# Wind_Weather_Station_V2_1.net
KiCad netlist of a schematic drawn in EAGLE
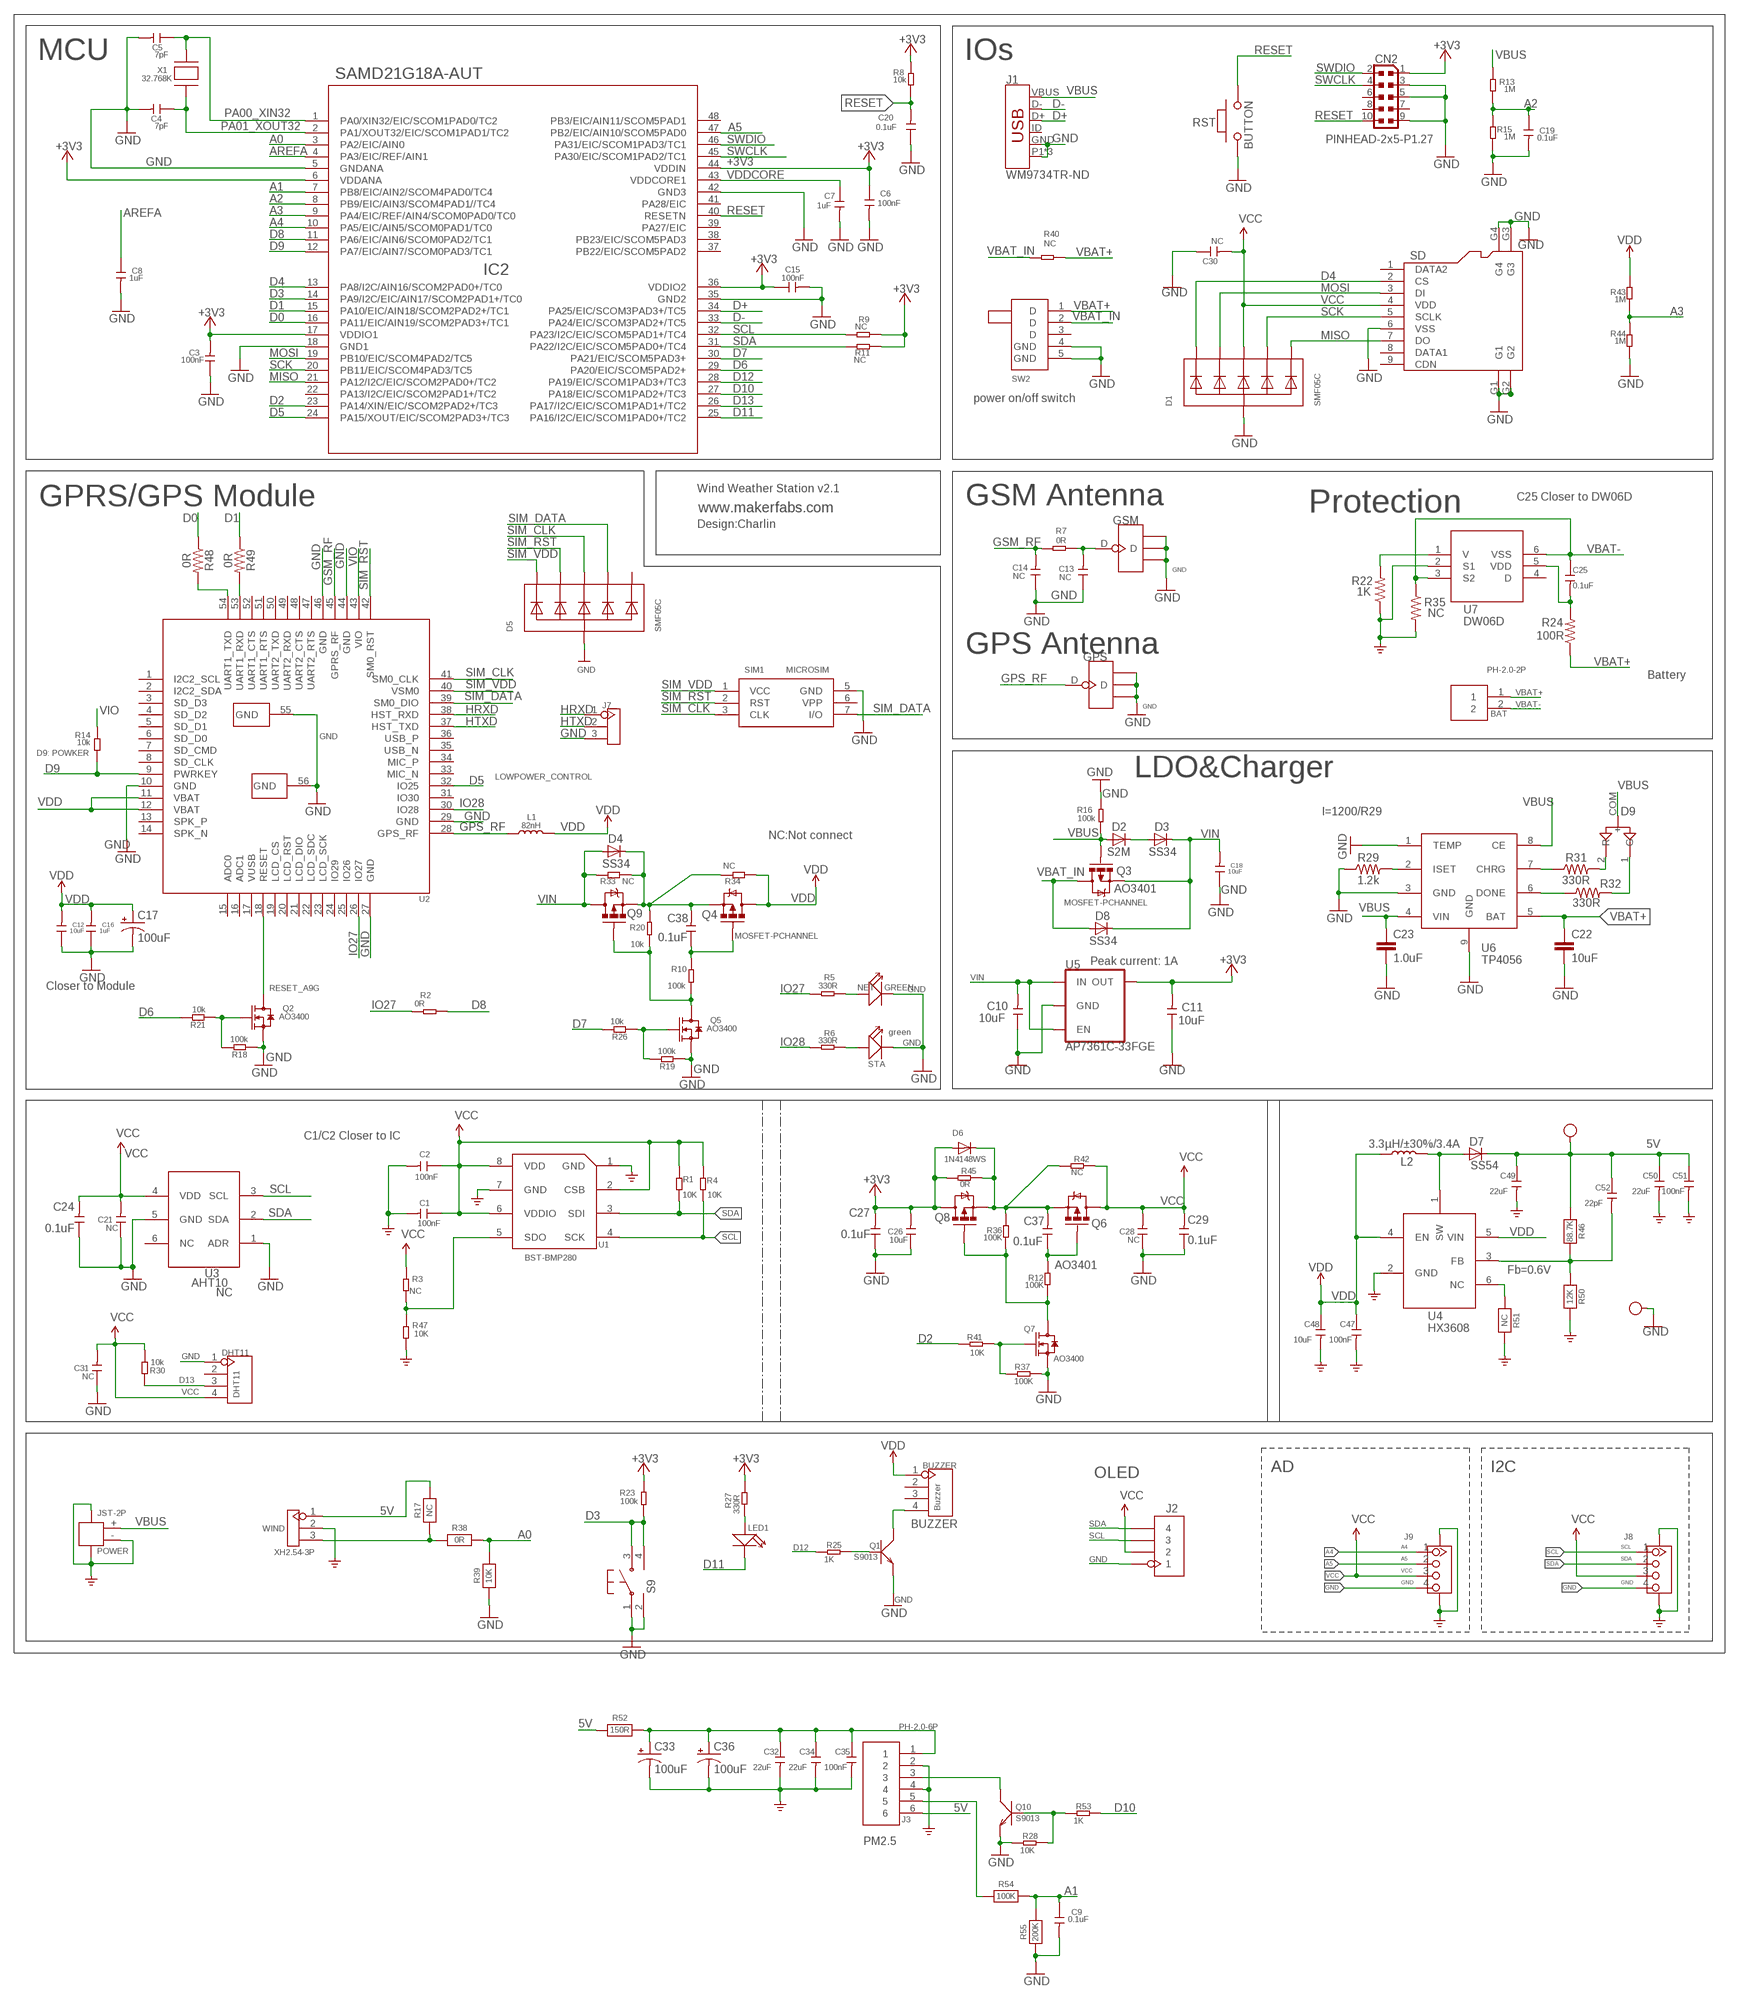
[diagram p0: schematic, sheet 1]

(export (version "E")
  (design (tool "Eeschema 10.0.6"))
  (components
    (comp (ref "5V")
      (value "TEST-POINT'4545'")
      (footprint "eagle-import:TP-D45MIL")
      (fields (field (name "PARTNO") "DNP"))
      (libsource (lib "eagle-import") (part "TEST-POINT'4545'"))
    )
    (comp (ref "BAT")
      (value "PH-2.0-2P")
      (footprint "eagle-import:PH-2.0-2P")
      (libsource (lib "eagle-import") (part "PH-2.0-2P"))
    )
    (comp (ref "BUZZER")
      (value "Buzzer")
      (footprint "eagle-import:4P-65_35ROUND")
      (libsource (lib "eagle-import") (part "HEADER-4P-60/35MILROUND"))
    )
    (comp (ref "C1")
      (value "100nF")
      (footprint "eagle-import:C0603")
      (libsource (lib "eagle-import") (part "CAP-0603"))
    )
    (comp (ref "C2")
      (value "100nF")
      (footprint "eagle-import:C0603")
      (libsource (lib "eagle-import") (part "CAP-0603"))
    )
    (comp (ref "C3")
      (value "100nF")
      (footprint "eagle-import:0603")
      (libsource (lib "eagle-import") (part "C-0603"))
    )
    (comp (ref "C4")
      (value "7pF")
      (footprint "eagle-import:0603")
      (libsource (lib "eagle-import") (part "C-0603"))
    )
    (comp (ref "C5")
      (value "7pF")
      (footprint "eagle-import:0603")
      (libsource (lib "eagle-import") (part "C-0603"))
    )
    (comp (ref "C6")
      (value "100nF")
      (footprint "eagle-import:0603")
      (libsource (lib "eagle-import") (part "C-0603"))
    )
    (comp (ref "C7")
      (value "1uF")
      (footprint "eagle-import:0603")
      (libsource (lib "eagle-import") (part "C-0603"))
    )
    (comp (ref "C8")
      (value "1uF")
      (footprint "eagle-import:0603")
      (libsource (lib "eagle-import") (part "C-0603"))
    )
    (comp (ref "C9")
      (value "0.1uF")
      (footprint "eagle-import:0603")
      (libsource (lib "eagle-import") (part "C-0603"))
    )
    (comp (ref "C10")
      (value "10uF")
      (footprint "eagle-import:0603")
      (libsource (lib "eagle-import") (part "C-0603"))
    )
    (comp (ref "C11")
      (value "10uF")
      (footprint "eagle-import:0603")
      (libsource (lib "eagle-import") (part "C-0603"))
    )
    (comp (ref "C12")
      (value "10uF")
      (footprint "eagle-import:0603")
      (libsource (lib "eagle-import") (part "C-0603"))
    )
    (comp (ref "C13")
      (value "NC")
      (footprint "eagle-import:0402")
      (libsource (lib "eagle-import") (part "C-0402"))
    )
    (comp (ref "C14")
      (value "NC")
      (footprint "eagle-import:0402")
      (libsource (lib "eagle-import") (part "C-0402"))
    )
    (comp (ref "C15")
      (value "100nF")
      (footprint "eagle-import:0603")
      (libsource (lib "eagle-import") (part "C-0603"))
    )
    (comp (ref "C16")
      (value "1uF")
      (footprint "eagle-import:0603")
      (libsource (lib "eagle-import") (part "C-0603"))
    )
    (comp (ref "C17")
      (value "100uF")
      (footprint "eagle-import:EIA3528")
      (libsource (lib "eagle-import") (part "68UF-POLAR-EIA3528-10V-10%(TANT)"))
    )
    (comp (ref "C18")
      (value "10uF")
      (footprint "eagle-import:0603")
      (libsource (lib "eagle-import") (part "C-0603"))
    )
    (comp (ref "C19")
      (value "0.1uF")
      (footprint "eagle-import:0603")
      (libsource (lib "eagle-import") (part "C-0603"))
    )
    (comp (ref "C20")
      (value "0.1uF")
      (footprint "eagle-import:0603")
      (libsource (lib "eagle-import") (part "C-0603"))
    )
    (comp (ref "C21")
      (value "NC")
      (footprint "eagle-import:0603")
      (libsource (lib "eagle-import") (part "C-0603"))
    )
    (comp (ref "C22")
      (value "10uF")
      (footprint "eagle-import:1206")
      (libsource (lib "eagle-import") (part "10UF-1206-6.3V-20%"))
    )
    (comp (ref "C23")
      (value "1.0uF")
      (footprint "eagle-import:0603")
      (libsource (lib "eagle-import") (part "1.0UF-0603-16V-10%"))
    )
    (comp (ref "C24")
      (value "0.1uF")
      (footprint "eagle-import:0603")
      (libsource (lib "eagle-import") (part "C-0603"))
    )
    (comp (ref "C25")
      (value "0.1uF")
      (footprint "eagle-import:0603")
      (libsource (lib "eagle-import") (part "C-0603"))
    )
    (comp (ref "C26")
      (value "10uF")
      (footprint "eagle-import:0603")
      (libsource (lib "eagle-import") (part "C-0603"))
    )
    (comp (ref "C27")
      (value "0.1uF")
      (footprint "eagle-import:0603")
      (libsource (lib "eagle-import") (part "C-0603"))
    )
    (comp (ref "C28")
      (value "NC")
      (footprint "eagle-import:0603")
      (libsource (lib "eagle-import") (part "C-0603"))
    )
    (comp (ref "C29")
      (value "0.1uF")
      (footprint "eagle-import:0603")
      (libsource (lib "eagle-import") (part "C-0603"))
    )
    (comp (ref "C30")
      (value "NC")
      (footprint "eagle-import:DISCRETE_C0603")
      (libsource (lib "eagle-import") (part "DISCRETE_C-0603"))
    )
    (comp (ref "C31")
      (value "NC")
      (footprint "eagle-import:0603")
      (libsource (lib "eagle-import") (part "C-0603"))
    )
    (comp (ref "C32")
      (value "22uF")
      (footprint "eagle-import:C0603")
      (libsource (lib "eagle-import") (part "CAP-0603"))
    )
    (comp (ref "C33")
      (value "100uF")
      (footprint "eagle-import:EIA3528")
      (fields (field (name "PROD_ID") "CAP-10790"))
      (libsource (lib "eagle-import") (part "68UF-POLAR-EIA3528-10V-10%(TANT)"))
    )
    (comp (ref "C34")
      (value "22uF")
      (footprint "eagle-import:C0603")
      (libsource (lib "eagle-import") (part "CAP-0603"))
    )
    (comp (ref "C35")
      (value "100nF")
      (footprint "eagle-import:C0603")
      (libsource (lib "eagle-import") (part "CAP-0603"))
    )
    (comp (ref "C36")
      (value "100uF")
      (footprint "eagle-import:EIA3528")
      (fields (field (name "PROD_ID") "CAP-10790"))
      (libsource (lib "eagle-import") (part "68UF-POLAR-EIA3528-10V-10%(TANT)"))
    )
    (comp (ref "C37")
      (value "0.1uF")
      (footprint "eagle-import:0603")
      (libsource (lib "eagle-import") (part "C-0603"))
    )
    (comp (ref "C38")
      (value "0.1uF")
      (footprint "eagle-import:0603")
      (libsource (lib "eagle-import") (part "C-0603"))
    )
    (comp (ref "C47")
      (value "100nF")
      (footprint "eagle-import:C0603")
      (libsource (lib "eagle-import") (part "CAP-0603"))
    )
    (comp (ref "C48")
      (value "10uF")
      (footprint "eagle-import:C0603")
      (libsource (lib "eagle-import") (part "CAP-0603"))
    )
    (comp (ref "C49")
      (value "22uF")
      (footprint "eagle-import:C0603")
      (libsource (lib "eagle-import") (part "CAP-0603"))
    )
    (comp (ref "C50")
      (value "22uF")
      (footprint "eagle-import:C0603")
      (libsource (lib "eagle-import") (part "CAP-0603"))
    )
    (comp (ref "C51")
      (value "100nF")
      (footprint "eagle-import:C0603")
      (libsource (lib "eagle-import") (part "CAP-0603"))
    )
    (comp (ref "C52")
      (value "22pF")
      (footprint "eagle-import:C0603")
      (libsource (lib "eagle-import") (part "CAP-0603"))
    )
    (comp (ref "CN2")
      (value "PINHEAD-2x5-P1.27")
      (footprint "eagle-import:PINHEAD_2X05_127")
      (libsource (lib "eagle-import") (part "0171_PH127-205DF055G00AROUND-PADS"))
    )
    (comp (ref "D1")
      (value "SMF05C")
      (footprint "eagle-import:SOT363")
      (libsource (lib "eagle-import") (part "TVSARRAY_5LANE"))
    )
    (comp (ref "D2")
      (value "S2M")
      (footprint "eagle-import:DO-214AC")
      (libsource (lib "eagle-import") (part "DIODE-DO-214AC"))
    )
    (comp (ref "D3")
      (value "SS34")
      (footprint "eagle-import:DO-214AC")
      (libsource (lib "eagle-import") (part "DIODE-DO-214AC"))
    )
    (comp (ref "D4")
      (value "SS34")
      (footprint "eagle-import:DO-214AC")
      (libsource (lib "eagle-import") (part "DIODE-DO-214AC"))
    )
    (comp (ref "D5")
      (value "SMF05C")
      (footprint "eagle-import:SOT363")
      (libsource (lib "eagle-import") (part "TVSARRAY_5LANE"))
    )
    (comp (ref "D6")
      (value "1N4148WS")
      (footprint "eagle-import:SOD-323F")
      (libsource (lib "eagle-import") (part "DIODESOD-323F"))
    )
    (comp (ref "D7")
      (value "SS54")
      (footprint "eagle-import:DO-214AC")
      (libsource (lib "eagle-import") (part "DIODE-DO-214AC"))
    )
    (comp (ref "D8")
      (value "SS34")
      (footprint "eagle-import:DO-214AC")
      (libsource (lib "eagle-import") (part "DIODE-DO-214AC"))
    )
    (comp (ref "D9")
      (value "LED-ARG-3P'-3MM'")
      (footprint "eagle-import:LED-3P-2.54-3MM")
      (libsource (lib "eagle-import") (part "LED-ARG-3P'-3MM'"))
    )
    (comp (ref "DHT11")
      (value "DHT11")
      (footprint "eagle-import:4P-65_35ROUND")
      (libsource (lib "eagle-import") (part "HEADER-4P-60/35MILROUND"))
    )
    (comp (ref "GND")
      (value "TEST-POINT'4545'")
      (footprint "eagle-import:TP-D45MIL")
      (fields (field (name "PARTNO") "DNP"))
      (libsource (lib "eagle-import") (part "TEST-POINT'4545'"))
    )
    (comp (ref "GPS")
      (value "ANTENNA-U-FL")
      (footprint "eagle-import:4P-U-FL")
      (libsource (lib "eagle-import") (part "ANTENNA-U-FL"))
    )
    (comp (ref "GSM")
      (value "ANTENNA-U-FL")
      (footprint "eagle-import:4P-U-FL")
      (libsource (lib "eagle-import") (part "ANTENNA-U-FL"))
    )
    (comp (ref "IC2")
      (value "SAMD21G18A-AUT")
      (footprint "eagle-import:TQFP48-7X7")
      (libsource (lib "eagle-import") (part "ATSAMD21G18A-AUT"))
    )
    (comp (ref "J1")
      (value "WM9734TR-ND")
      (footprint "eagle-import:USB-B-MICRO-SMD_VERT")
      (libsource (lib "eagle-import") (part "USB_MICRO-B_FEMALE-SMT-VERT"))
    )
    (comp (ref "J2")
      (value "HEADER-1X4P")
      (footprint "eagle-import:SMD4-2.54P")
      (libsource (lib "eagle-import") (part "HEADER-1X4P"))
    )
    (comp (ref "J3")
      (value "PH-2.0-6P")
      (footprint "eagle-import:PH-2.0-6P")
      (libsource (lib "eagle-import") (part "PH-2.0-6P"))
    )
    (comp (ref "J7")
      (value "HEADER-3P-2.54")
      (footprint "eagle-import:3P-2.54")
      (libsource (lib "eagle-import") (part "HEADER-3P-2.54"))
    )
    (comp (ref "J8")
      (value "GROVE-CONNECTOR-SMD'90D'")
      (footprint "eagle-import:HW4-SMD-2.0-90D")
      (libsource (lib "eagle-import") (part "GROVE-CONNECTOR-SMD'90D'"))
    )
    (comp (ref "J9")
      (value "GROVE-CONNECTOR-SMD'90D'")
      (footprint "eagle-import:HW4-SMD-2.0-90D")
      (libsource (lib "eagle-import") (part "GROVE-CONNECTOR-SMD'90D'"))
    )
    (comp (ref "L1")
      (value "82nH")
      (footprint "eagle-import:L0603")
      (libsource (lib "eagle-import") (part "L'0603'"))
    )
    (comp (ref "L2")
      (value "3.3µH/±30%/3.4A")
      (footprint "eagle-import:CR54")
      (libsource (lib "eagle-import") (part "INDUCTOR-CR54-3.3UH"))
    )
    (comp (ref "LED1")
      (value "DISCRETE_LED0603")
      (footprint "eagle-import:DISCRETE_LED-0603")
      (libsource (lib "eagle-import") (part "DISCRETE_LED0603"))
    )
    (comp (ref "NET")
      (value "GREEN")
      (footprint "eagle-import:DISCRETE_LED-0603")
      (libsource (lib "eagle-import") (part "DISCRETE_LED0603"))
    )
    (comp (ref "POWER")
      (value "JST-2P")
      (footprint "eagle-import:HW2-SMD-2.0-90D")
      (libsource (lib "eagle-import") (part "JST-2P-SMD'2.0'"))
    )
    (comp (ref "Q1")
      (value "S9013")
      (footprint "eagle-import:SOT23")
      (libsource (lib "eagle-import") (part "TRANSISTOR-NPN-SOT23"))
    )
    (comp (ref "Q2")
      (value "AO3400")
      (footprint "eagle-import:SOT23@1")
      (libsource (lib "eagle-import") (part "MOSFET-N'SOT23'"))
    )
    (comp (ref "Q3")
      (value "MOSFET-PCHANNEL")
      (footprint "eagle-import:SOT23-3")
      (libsource (lib "eagle-import") (part "MOSFET-PCHANNEL"))
    )
    (comp (ref "Q4")
      (value "MOSFET-PCHANNEL")
      (footprint "eagle-import:SOT23-3")
      (fields (field (name "PROD_ID") "TRANS-08285"))
      (libsource (lib "eagle-import") (part "MOSFET-PCHANNEL"))
    )
    (comp (ref "Q5")
      (value "AO3400")
      (footprint "eagle-import:SOT23@1")
      (libsource (lib "eagle-import") (part "MOSFET-N'SOT23'"))
    )
    (comp (ref "Q6")
      (value "MOSFET-PCHANNEL")
      (footprint "eagle-import:SOT23-3")
      (libsource (lib "eagle-import") (part "MOSFET-PCHANNEL"))
    )
    (comp (ref "Q7")
      (value "AO3400")
      (footprint "eagle-import:DISCRETE_SOT23")
      (libsource (lib "eagle-import") (part "DISCRETE_MOSFET-NSOT23"))
    )
    (comp (ref "Q8")
      (value "MOSFET-PCHANNEL")
      (footprint "eagle-import:SOT23-3")
      (fields (field (name "PROD_ID") "TRANS-08285"))
      (libsource (lib "eagle-import") (part "MOSFET-PCHANNEL"))
    )
    (comp (ref "Q9")
      (value "MOSFET-PCHANNEL")
      (footprint "eagle-import:SOT23-3")
      (fields (field (name "PROD_ID") "TRANS-08285"))
      (libsource (lib "eagle-import") (part "MOSFET-PCHANNEL"))
    )
    (comp (ref "Q10")
      (value "S9013")
      (footprint "eagle-import:SOT23")
      (libsource (lib "eagle-import") (part "TRANSISTOR-NPN-SOT23"))
    )
    (comp (ref "R1")
      (value "10K")
      (footprint "eagle-import:R0603")
      (libsource (lib "eagle-import") (part "RES-0603"))
    )
    (comp (ref "R2")
      (value "0R")
      (footprint "eagle-import:R0603")
      (libsource (lib "eagle-import") (part "R-0603"))
    )
    (comp (ref "R3")
      (value "NC")
      (footprint "eagle-import:R0603")
      (libsource (lib "eagle-import") (part "RES-0603"))
    )
    (comp (ref "R4")
      (value "10K")
      (footprint "eagle-import:R0603")
      (libsource (lib "eagle-import") (part "RES-0603"))
    )
    (comp (ref "R5")
      (value "330R")
      (footprint "eagle-import:R0603")
      (libsource (lib "eagle-import") (part "R-0603"))
    )
    (comp (ref "R6")
      (value "330R")
      (footprint "eagle-import:R0603")
      (libsource (lib "eagle-import") (part "R-0603"))
    )
    (comp (ref "R7")
      (value "0R")
      (footprint "eagle-import:R0603")
      (libsource (lib "eagle-import") (part "R-0603"))
    )
    (comp (ref "R8")
      (value "10k")
      (footprint "eagle-import:R0603")
      (libsource (lib "eagle-import") (part "R-0603"))
    )
    (comp (ref "R9")
      (value "NC")
      (footprint "eagle-import:R0603")
      (libsource (lib "eagle-import") (part "R-0603"))
    )
    (comp (ref "R10")
      (value "100k")
      (footprint "eagle-import:R0603")
      (libsource (lib "eagle-import") (part "R-0603"))
    )
    (comp (ref "R11")
      (value "NC")
      (footprint "eagle-import:R0603")
      (libsource (lib "eagle-import") (part "R-0603"))
    )
    (comp (ref "R12")
      (value "100K")
      (footprint "eagle-import:R0603")
      (libsource (lib "eagle-import") (part "R-0603"))
    )
    (comp (ref "R13")
      (value "1M")
      (footprint "eagle-import:R0603")
      (libsource (lib "eagle-import") (part "R-0603"))
    )
    (comp (ref "R14")
      (value "10k")
      (footprint "eagle-import:R0603")
      (libsource (lib "eagle-import") (part "R-0603"))
    )
    (comp (ref "R15")
      (value "1M")
      (footprint "eagle-import:R0603")
      (libsource (lib "eagle-import") (part "R-0603"))
    )
    (comp (ref "R16")
      (value "100k")
      (footprint "eagle-import:R0603")
      (libsource (lib "eagle-import") (part "R-0603"))
    )
    (comp (ref "R17")
      (value "NC")
      (footprint "eagle-import:0603-NO")
      (libsource (lib "eagle-import") (part "RESISTOR_0603_NOOUT"))
    )
    (comp (ref "R18")
      (value "100k")
      (footprint "eagle-import:R0603")
      (libsource (lib "eagle-import") (part "R-0603"))
    )
    (comp (ref "R19")
      (value "100k")
      (footprint "eagle-import:R0603")
      (libsource (lib "eagle-import") (part "R-0603"))
    )
    (comp (ref "R20")
      (value "10k")
      (footprint "eagle-import:R0603")
      (libsource (lib "eagle-import") (part "R-0603"))
    )
    (comp (ref "R21")
      (value "10k")
      (footprint "eagle-import:R0603")
      (libsource (lib "eagle-import") (part "R-0603"))
    )
    (comp (ref "R22")
      (value "1K")
      (footprint "eagle-import:0603")
      (fields (field (name "PROD_ID") "RES-00824"))
      (libsource (lib "eagle-import") (part "10KOHM-0603-1/10W-1%"))
    )
    (comp (ref "R23")
      (value "100k")
      (footprint "eagle-import:R0603")
      (libsource (lib "eagle-import") (part "R-0603"))
    )
    (comp (ref "R24")
      (value "100R")
      (footprint "eagle-import:0603")
      (fields (field (name "PROD_ID") "RES-00824"))
      (libsource (lib "eagle-import") (part "10KOHM-0603-1/10W-1%"))
    )
    (comp (ref "R25")
      (value "1K")
      (footprint "eagle-import:R0603")
      (libsource (lib "eagle-import") (part "R-0603"))
    )
    (comp (ref "R26")
      (value "10k")
      (footprint "eagle-import:R0603")
      (libsource (lib "eagle-import") (part "R-0603"))
    )
    (comp (ref "R27")
      (value "330R")
      (footprint "eagle-import:R0603")
      (libsource (lib "eagle-import") (part "R-0603"))
    )
    (comp (ref "R28")
      (value "10K")
      (footprint "eagle-import:R0603")
      (libsource (lib "eagle-import") (part "R-0603"))
    )
    (comp (ref "R29")
      (value "1.2k")
      (footprint "eagle-import:0603")
      (libsource (lib "eagle-import") (part "2.49KOHM-0603-1/10W-1%"))
    )
    (comp (ref "R30")
      (value "10k")
      (footprint "eagle-import:R0603")
      (libsource (lib "eagle-import") (part "R-0603"))
    )
    (comp (ref "R31")
      (value "330R")
      (footprint "eagle-import:0603")
      (libsource (lib "eagle-import") (part "330OHM-0603-1/10W-1%"))
    )
    (comp (ref "R32")
      (value "330R")
      (footprint "eagle-import:0603")
      (libsource (lib "eagle-import") (part "330OHM-0603-1/10W-1%"))
    )
    (comp (ref "R33")
      (value "NC")
      (footprint "eagle-import:R0603")
      (libsource (lib "eagle-import") (part "R-0603"))
    )
    (comp (ref "R34")
      (value "NC")
      (footprint "eagle-import:R0603")
      (libsource (lib "eagle-import") (part "R-0603"))
    )
    (comp (ref "R35")
      (value "NC")
      (footprint "eagle-import:0603")
      (fields (field (name "PROD_ID") "RES-00824"))
      (libsource (lib "eagle-import") (part "10KOHM-0603-1/10W-1%"))
    )
    (comp (ref "R36")
      (value "100K")
      (footprint "eagle-import:R0603")
      (libsource (lib "eagle-import") (part "R-0603"))
    )
    (comp (ref "R37")
      (value "100K")
      (footprint "eagle-import:R0603")
      (libsource (lib "eagle-import") (part "R-0603"))
    )
    (comp (ref "R38")
      (value "0R")
      (footprint "eagle-import:0603-NO")
      (libsource (lib "eagle-import") (part "RESISTOR_0603_NOOUT"))
    )
    (comp (ref "R39")
      (value "10K")
      (footprint "eagle-import:0603-NO")
      (libsource (lib "eagle-import") (part "RESISTOR_0603_NOOUT"))
    )
    (comp (ref "R40")
      (value "NC")
      (footprint "eagle-import:R0603")
      (libsource (lib "eagle-import") (part "R-0603"))
    )
    (comp (ref "R41")
      (value "10K")
      (footprint "eagle-import:R0603")
      (libsource (lib "eagle-import") (part "R-0603"))
    )
    (comp (ref "R42")
      (value "NC")
      (footprint "eagle-import:R0603")
      (libsource (lib "eagle-import") (part "R-0603"))
    )
    (comp (ref "R43")
      (value "1M")
      (footprint "eagle-import:R0603")
      (libsource (lib "eagle-import") (part "R-0603"))
    )
    (comp (ref "R44")
      (value "1M")
      (footprint "eagle-import:R0603")
      (libsource (lib "eagle-import") (part "R-0603"))
    )
    (comp (ref "R45")
      (value "0R")
      (footprint "eagle-import:R0603")
      (libsource (lib "eagle-import") (part "R-0603"))
    )
    (comp (ref "R46")
      (value "88.7K")
      (footprint "eagle-import:0603-NO")
      (libsource (lib "eagle-import") (part "RESISTOR_0603_NOOUT"))
    )
    (comp (ref "R47")
      (value "10K")
      (footprint "eagle-import:R0603")
      (libsource (lib "eagle-import") (part "RES-0603"))
    )
    (comp (ref "R48")
      (value "0R")
      (footprint "eagle-import:0603")
      (fields (field (name "PROD_ID") "RES-07857"))
      (libsource (lib "eagle-import") (part "4.7KOHM-0603-1/10W-1%"))
    )
    (comp (ref "R49")
      (value "0R")
      (footprint "eagle-import:0603")
      (fields (field (name "PROD_ID") "RES-07857"))
      (libsource (lib "eagle-import") (part "4.7KOHM-0603-1/10W-1%"))
    )
    (comp (ref "R50")
      (value "12K")
      (footprint "eagle-import:0603-NO")
      (libsource (lib "eagle-import") (part "RESISTOR_0603_NOOUT"))
    )
    (comp (ref "R51")
      (value "NC")
      (footprint "eagle-import:0603-NO")
      (libsource (lib "eagle-import") (part "RESISTOR_0603_NOOUT"))
    )
    (comp (ref "R52")
      (value "150R")
      (footprint "eagle-import:0603-NO")
      (libsource (lib "eagle-import") (part "RESISTOR_0603_NOOUT"))
    )
    (comp (ref "R53")
      (value "1K")
      (footprint "eagle-import:R0603")
      (libsource (lib "eagle-import") (part "R-0603"))
    )
    (comp (ref "R54")
      (value "100K")
      (footprint "eagle-import:0603-NO")
      (libsource (lib "eagle-import") (part "RESISTOR_0603_NOOUT"))
    )
    (comp (ref "R55")
      (value "200K")
      (footprint "eagle-import:0603-NO")
      (libsource (lib "eagle-import") (part "RESISTOR_0603_NOOUT"))
    )
    (comp (ref "RST")
      (value "BUTTON")
      (footprint "eagle-import:157SW")
      (libsource (lib "eagle-import") (part "PB157"))
    )
    (comp (ref "S9")
      (value "SWITCHES")
      (footprint "eagle-import:SMD4-6_6")
      (libsource (lib "eagle-import") (part "SWITCHES"))
    )
    (comp (ref "SD")
      (value "HOLDER-MICROSD-9P")
      (footprint "eagle-import:9P-SMD-W_-RING")
      (libsource (lib "eagle-import") (part "HOLDER-MICROSD-9P"))
    )
    (comp (ref "SIM1")
      (value "MICROSIM")
      (footprint "eagle-import:MICROSIM")
      (libsource (lib "eagle-import") (part "MICROSIM"))
    )
    (comp (ref "STA")
      (value "green")
      (footprint "eagle-import:LED-0603")
      (libsource (lib "eagle-import") (part "LED'0603'"))
    )
    (comp (ref "SW2")
      (value "SWITCH")
      (footprint "eagle-import:DIP5-8.6_4.5MM")
      (libsource (lib "eagle-import") (part "SWITCH"))
    )
    (comp (ref "U1")
      (value "BST-BMP280")
      (footprint "eagle-import:LGA8-0.65-2X2.5X0.95MM")
      (fields (field (name "MPN") "BMP280"))
      (libsource (lib "eagle-import") (part "SENSOR-BMP280"))
    )
    (comp (ref "U2")
      (value "A9G")
      (footprint "eagle-import:A9G")
      (libsource (lib "eagle-import") (part "A9G"))
    )
    (comp (ref "U3")
      (value "AHT10")
      (footprint "eagle-import:SMD6-127P-400L500W")
      (libsource (lib "eagle-import") (part "AHT10"))
    )
    (comp (ref "U4")
      (value "HX3608")
      (footprint "eagle-import:SOT-23-6")
      (libsource (lib "eagle-import") (part "HX3608"))
    )
    (comp (ref "U5")
      (value "AP7361C-33FGE")
      (footprint "eagle-import:8-UDFN")
      (libsource (lib "eagle-import") (part "AP7361C-33FGE"))
    )
    (comp (ref "U6")
      (value "TP4056")
      (footprint "eagle-import:SOP8-1.27P")
      (libsource (lib "eagle-import") (part "TP4056"))
    )
    (comp (ref "U7")
      (value "DW06D")
      (footprint "eagle-import:SOT-23-6")
      (libsource (lib "eagle-import") (part "DW06D"))
    )
    (comp (ref "WIND")
      (value "XH2.54-3P")
      (footprint "eagle-import:XH2.54-3P")
      (libsource (lib "eagle-import") (part "XH2.54-3P"))
    )
    (comp (ref "X1")
      (value "32.768K")
      (footprint "eagle-import:XTAL3215")
      (libsource (lib "eagle-import") (part "XTAL-3.2X1.5"))
    )
  )
  (nets
    (net (code "1") (name "+3V3") (class "Default")
      (node (ref "C11") (pin "2") (pinfunction "2_2") (pintype "passive"))
      (node (ref "C15") (pin "1") (pinfunction "1_1") (pintype "passive"))
      (node (ref "C26") (pin "2") (pinfunction "2_2") (pintype "passive"))
      (node (ref "C27") (pin "2") (pinfunction "2_2") (pintype "passive"))
      (node (ref "C3") (pin "2") (pinfunction "2_2") (pintype "passive"))
      (node (ref "C6") (pin "1") (pinfunction "1_1") (pintype "passive"))
      (node (ref "CN2") (pin "1") (pinfunction "1_1") (pintype "passive"))
      (node (ref "D6") (pin "A") (pinfunction "A_A") (pintype "passive"))
      (node (ref "IC2") (pin "17") (pinfunction "VDDIO1_17") (pintype "power_in"))
      (node (ref "IC2") (pin "36") (pinfunction "VDDIO2_36") (pintype "power_in"))
      (node (ref "IC2") (pin "44") (pinfunction "VDDIN_44") (pintype "power_in"))
      (node (ref "IC2") (pin "6") (pinfunction "VDDANA_6") (pintype "power_in"))
      (node (ref "Q8") (pin "3") (pinfunction "D_3") (pintype "passive"))
      (node (ref "R11") (pin "2") (pinfunction "2_2") (pintype "passive"))
      (node (ref "R23") (pin "2") (pinfunction "2_2") (pintype "passive"))
      (node (ref "R27") (pin "2") (pinfunction "2_2") (pintype "passive"))
      (node (ref "R45") (pin "2") (pinfunction "2_2") (pintype "passive"))
      (node (ref "R8") (pin "2") (pinfunction "2_2") (pintype "passive"))
      (node (ref "R9") (pin "2") (pinfunction "2_2") (pintype "passive"))
      (node (ref "U5") (pin "1") (pinfunction "OUT_1") (pintype "output"))
    )
    (net (code "2") (name "/5V") (class "Default")
      (node (ref "5V") (pin "T") (pinfunction "T_T") (pintype "bidirectional"))
      (node (ref "C49") (pin "1") (pinfunction "1_1") (pintype "passive"))
      (node (ref "C50") (pin "1") (pinfunction "1_1") (pintype "passive"))
      (node (ref "C51") (pin "1") (pinfunction "1_1") (pintype "passive"))
      (node (ref "C52") (pin "1") (pinfunction "1_1") (pintype "passive"))
      (node (ref "D7") (pin "C") (pinfunction "C_C") (pintype "passive"))
      (node (ref "J3") (pin "6") (pinfunction "6_6") (pintype "bidirectional"))
      (node (ref "R17") (pin "2") (pinfunction "2_2") (pintype "passive"))
      (node (ref "R46") (pin "1") (pinfunction "1_1") (pintype "passive"))
      (node (ref "R52") (pin "1") (pinfunction "1_1") (pintype "passive"))
      (node (ref "WIND") (pin "1") (pinfunction "P$1_1") (pintype "bidirectional"))
    )
    (net (code "3") (name "/A0") (class "Default")
      (node (ref "IC2") (pin "3") (pinfunction "PA2/EIC/AIN0_3") (pintype "bidirectional"))
      (node (ref "R38") (pin "2") (pinfunction "2_2") (pintype "passive"))
      (node (ref "R39") (pin "2") (pinfunction "2_2") (pintype "passive"))
    )
    (net (code "4") (name "/A1") (class "Default")
      (node (ref "C9") (pin "1") (pinfunction "1_1") (pintype "passive"))
      (node (ref "IC2") (pin "7") (pinfunction "PB8/EIC/AIN2/SCOM4PAD0/TC4_7") (pintype "bidirectional"))
      (node (ref "R54") (pin "2") (pinfunction "2_2") (pintype "passive"))
      (node (ref "R55") (pin "2") (pinfunction "2_2") (pintype "passive"))
    )
    (net (code "5") (name "/A2") (class "Default")
      (node (ref "C19") (pin "1") (pinfunction "1_1") (pintype "passive"))
      (node (ref "IC2") (pin "8") (pinfunction "PB9/EIC/AIN3/SCOM4PAD1//TC4_8") (pintype "bidirectional"))
      (node (ref "R13") (pin "1") (pinfunction "1_1") (pintype "passive"))
      (node (ref "R15") (pin "2") (pinfunction "2_2") (pintype "passive"))
    )
    (net (code "6") (name "/A3") (class "Default")
      (node (ref "IC2") (pin "9") (pinfunction "PA4/EIC/REF/AIN4/SCOM0PAD0/TC0_9") (pintype "bidirectional"))
      (node (ref "R43") (pin "1") (pinfunction "1_1") (pintype "passive"))
      (node (ref "R44") (pin "2") (pinfunction "2_2") (pintype "passive"))
    )
    (net (code "7") (name "/AREFA") (class "Default")
      (node (ref "C8") (pin "1") (pinfunction "1_1") (pintype "passive"))
      (node (ref "IC2") (pin "4") (pinfunction "PA3/EIC/REF/AIN1_4") (pintype "bidirectional"))
    )
    (net (code "8") (name "/D+") (class "Default")
      (node (ref "IC2") (pin "34") (pinfunction "PA25/EIC/SCOM3PAD3+/TC5_34") (pintype "bidirectional"))
      (node (ref "J1") (pin "D+") (pinfunction "D+_D+") (pintype "bidirectional"))
    )
    (net (code "9") (name "/D-") (class "Default")
      (node (ref "IC2") (pin "33") (pinfunction "PA24/EIC/SCOM3PAD2+/TC5_33") (pintype "bidirectional"))
      (node (ref "J1") (pin "D-") (pinfunction "D-_D-") (pintype "bidirectional"))
    )
    (net (code "10") (name "/D0") (class "Default")
      (node (ref "IC2") (pin "16") (pinfunction "PA11/EIC/AIN19/SCOM2PAD3+/TC1_16") (pintype "bidirectional"))
      (node (ref "R48") (pin "1") (pinfunction "1_1") (pintype "passive"))
    )
    (net (code "11") (name "/D1") (class "Default")
      (node (ref "IC2") (pin "15") (pinfunction "PA10/EIC/AIN18/SCOM2PAD2+/TC1_15") (pintype "bidirectional"))
      (node (ref "R49") (pin "1") (pinfunction "1_1") (pintype "passive"))
    )
    (net (code "12") (name "/D2") (class "Default")
      (node (ref "IC2") (pin "23") (pinfunction "PA14/XIN/EIC/SCOM2PAD2+/TC3_23") (pintype "bidirectional"))
      (node (ref "R41") (pin "2") (pinfunction "2_2") (pintype "passive"))
    )
    (net (code "13") (name "/D3") (class "Default")
      (node (ref "IC2") (pin "14") (pinfunction "PA9/I2C/EIC/AIN17/SCOM2PAD1+/TC0_14") (pintype "bidirectional"))
      (node (ref "R23") (pin "1") (pinfunction "1_1") (pintype "passive"))
      (node (ref "S9") (pin "3") (pinfunction "3_3") (pintype "bidirectional"))
      (node (ref "S9") (pin "4") (pinfunction "4_4") (pintype "bidirectional"))
    )
    (net (code "14") (name "/D4") (class "Default")
      (node (ref "D1") (pin "1") (pinfunction "C1_1") (pintype "passive"))
      (node (ref "IC2") (pin "13") (pinfunction "PA8/I2C/AIN16/SCOM2PAD0+/TC0_13") (pintype "bidirectional"))
      (node (ref "SD") (pin "2") (pinfunction "CS_2") (pintype "bidirectional"))
    )
    (net (code "15") (name "/D5") (class "Default")
      (node (ref "IC2") (pin "24") (pinfunction "PA15/XOUT/EIC/SCOM2PAD3+/TC3_24") (pintype "bidirectional"))
      (node (ref "U2") (pin "32") (pinfunction "IO25_32") (pintype "bidirectional"))
    )
    (net (code "16") (name "/D6") (class "Default")
      (node (ref "IC2") (pin "29") (pinfunction "PA20/EIC/SCOM5PAD2+_29") (pintype "bidirectional"))
      (node (ref "R21") (pin "2") (pinfunction "2_2") (pintype "passive"))
    )
    (net (code "17") (name "/D7") (class "Default")
      (node (ref "IC2") (pin "30") (pinfunction "PA21/EIC/SCOM5PAD3+_30") (pintype "bidirectional"))
      (node (ref "R26") (pin "2") (pinfunction "2_2") (pintype "passive"))
    )
    (net (code "18") (name "/D8") (class "Default")
      (node (ref "IC2") (pin "11") (pinfunction "PA6/EIC/AIN6/SCOM0PAD2/TC1_11") (pintype "bidirectional"))
      (node (ref "R2") (pin "2") (pinfunction "2_2") (pintype "passive"))
    )
    (net (code "19") (name "/D9") (class "Default")
      (node (ref "IC2") (pin "12") (pinfunction "PA7/EIC/AIN7/SCOM0PAD3/TC1_12") (pintype "bidirectional"))
      (node (ref "R14") (pin "1") (pinfunction "1_1") (pintype "passive"))
      (node (ref "U2") (pin "9") (pinfunction "PWRKEY_9") (pintype "bidirectional"))
    )
    (net (code "20") (name "/D10") (class "Default")
      (node (ref "IC2") (pin "27") (pinfunction "PA18/EIC/SCOM1PAD2+/TC3_27") (pintype "bidirectional"))
      (node (ref "R53") (pin "2") (pinfunction "2_2") (pintype "passive"))
    )
    (net (code "21") (name "/D11") (class "Default")
      (node (ref "IC2") (pin "25") (pinfunction "PA16/I2C/EIC/SCOM1PAD0+/TC2_25") (pintype "bidirectional"))
      (node (ref "LED1") (pin "-") (pinfunction "-_-") (pintype "passive"))
    )
    (net (code "22") (name "/D12") (class "Default")
      (node (ref "IC2") (pin "28") (pinfunction "PA19/EIC/SCOM1PAD3+/TC3_28") (pintype "bidirectional"))
      (node (ref "R25") (pin "1") (pinfunction "1_1") (pintype "passive"))
    )
    (net (code "23") (name "/D13") (class "Default")
      (node (ref "DHT11") (pin "3") (pinfunction "P$3_3") (pintype "bidirectional"))
      (node (ref "IC2") (pin "26") (pinfunction "PA17/I2C/EIC/SCOM1PAD1+/TC2_26") (pintype "bidirectional"))
      (node (ref "R30") (pin "1") (pinfunction "1_1") (pintype "passive"))
    )
    (net (code "24") (name "/GPS_RF") (class "Default")
      (node (ref "GPS") (pin "D") (pinfunction "D_D") (pintype "bidirectional"))
      (node (ref "L1") (pin "1") (pinfunction "1_1") (pintype "passive"))
      (node (ref "U2") (pin "28") (pinfunction "GPS_RF_28") (pintype "bidirectional"))
    )
    (net (code "25") (name "/GSM_RF") (class "Default")
      (node (ref "C14") (pin "2") (pinfunction "2_2") (pintype "passive"))
      (node (ref "R7") (pin "1") (pinfunction "1_1") (pintype "passive"))
      (node (ref "U2") (pin "45") (pinfunction "GPRS_RF_45") (pintype "bidirectional"))
    )
    (net (code "26") (name "/HRXD") (class "Default")
      (node (ref "J7") (pin "1") (pinfunction "P$1_1") (pintype "bidirectional"))
      (node (ref "U2") (pin "38") (pinfunction "HST_RXD_38") (pintype "bidirectional"))
    )
    (net (code "27") (name "/HTXD") (class "Default")
      (node (ref "J7") (pin "2") (pinfunction "P$2_2") (pintype "bidirectional"))
      (node (ref "U2") (pin "37") (pinfunction "HST_TXD_37") (pintype "bidirectional"))
    )
    (net (code "28") (name "/IO27") (class "Default")
      (node (ref "R2") (pin "1") (pinfunction "1_1") (pintype "passive"))
      (node (ref "R5") (pin "1") (pinfunction "1_1") (pintype "passive"))
      (node (ref "U2") (pin "26") (pinfunction "IO27_26") (pintype "bidirectional"))
    )
    (net (code "29") (name "/IO28") (class "Default")
      (node (ref "R6") (pin "1") (pinfunction "1_1") (pintype "passive"))
      (node (ref "U2") (pin "30") (pinfunction "IO28_30") (pintype "bidirectional"))
    )
    (net (code "30") (name "/MISO") (class "Default")
      (node (ref "D1") (pin "6") (pinfunction "C5_6") (pintype "passive"))
      (node (ref "IC2") (pin "21") (pinfunction "PA12/I2C/EIC/SCOM2PAD0+/TC2_21") (pintype "bidirectional"))
      (node (ref "SD") (pin "7") (pinfunction "DO_7") (pintype "bidirectional"))
    )
    (net (code "31") (name "/MOSI") (class "Default")
      (node (ref "D1") (pin "3") (pinfunction "C2_3") (pintype "passive"))
      (node (ref "IC2") (pin "19") (pinfunction "PB10/EIC/SCOM4PAD2/TC5_19") (pintype "bidirectional"))
      (node (ref "SD") (pin "3") (pinfunction "DI_3") (pintype "bidirectional"))
    )
    (net (code "32") (name "/PA00_XIN32") (class "Default")
      (node (ref "C5") (pin "1") (pinfunction "1_1") (pintype "passive"))
      (node (ref "IC2") (pin "1") (pinfunction "PA0/XIN32/EIC/SCOM1PAD0/TC2_1") (pintype "bidirectional"))
      (node (ref "X1") (pin "P$2") (pinfunction "P$2_P$2") (pintype "bidirectional"))
    )
    (net (code "33") (name "/PA01_XOUT32") (class "Default")
      (node (ref "C4") (pin "1") (pinfunction "1_1") (pintype "passive"))
      (node (ref "IC2") (pin "2") (pinfunction "PA1/XOUT32/EIC/SCOM1PAD1/TC2_2") (pintype "bidirectional"))
      (node (ref "X1") (pin "P$1") (pinfunction "P$1_P$1") (pintype "bidirectional"))
    )
    (net (code "34") (name "/SCK") (class "Default")
      (node (ref "D1") (pin "5") (pinfunction "C4_5") (pintype "passive"))
      (node (ref "IC2") (pin "20") (pinfunction "PB11/EIC/SCOM4PAD3/TC5_20") (pintype "bidirectional"))
      (node (ref "SD") (pin "5") (pinfunction "SCLK_5") (pintype "bidirectional"))
    )
    (net (code "35") (name "/SIM_CLK") (class "Default")
      (node (ref "D5") (pin "4") (pinfunction "C3_4") (pintype "passive"))
      (node (ref "SIM1") (pin "3") (pinfunction "CLK_3") (pintype "bidirectional"))
      (node (ref "U2") (pin "41") (pinfunction "SM0_CLK_41") (pintype "bidirectional"))
    )
    (net (code "36") (name "/SIM_DATA") (class "Default")
      (node (ref "D5") (pin "5") (pinfunction "C4_5") (pintype "passive"))
      (node (ref "SIM1") (pin "7") (pinfunction "I/O_7") (pintype "bidirectional"))
      (node (ref "U2") (pin "39") (pinfunction "SM0_DIO_39") (pintype "bidirectional"))
    )
    (net (code "37") (name "/SIM_RST") (class "Default")
      (node (ref "D5") (pin "3") (pinfunction "C2_3") (pintype "passive"))
      (node (ref "SIM1") (pin "2") (pinfunction "RST_2") (pintype "bidirectional"))
      (node (ref "U2") (pin "42") (pinfunction "SM0_RST_42") (pintype "bidirectional"))
    )
    (net (code "38") (name "/SIM_VDD") (class "Default")
      (node (ref "D5") (pin "1") (pinfunction "C1_1") (pintype "passive"))
      (node (ref "SIM1") (pin "1") (pinfunction "VCC_1") (pintype "bidirectional"))
      (node (ref "U2") (pin "40") (pinfunction "VSM0_40") (pintype "bidirectional"))
    )
    (net (code "39") (name "/SWCLK") (class "Default")
      (node (ref "CN2") (pin "4") (pinfunction "4_4") (pintype "passive"))
      (node (ref "IC2") (pin "45") (pinfunction "PA30/EIC/SCOM1PAD2/TC1_45") (pintype "bidirectional"))
    )
    (net (code "40") (name "/SWDIO") (class "Default")
      (node (ref "CN2") (pin "2") (pinfunction "2_2") (pintype "passive"))
      (node (ref "IC2") (pin "46") (pinfunction "PA31/EIC/SCOM1PAD3/TC1_46") (pintype "bidirectional"))
    )
    (net (code "41") (name "/VBAT-") (class "Default")
      (node (ref "BAT") (pin "2") (pinfunction "2_2") (pintype "bidirectional"))
      (node (ref "C25") (pin "1") (pinfunction "1_1") (pintype "passive"))
      (node (ref "R35") (pin "1") (pinfunction "1_1") (pintype "passive"))
      (node (ref "U7") (pin "3") (pinfunction "S2_3") (pintype "bidirectional"))
      (node (ref "U7") (pin "6") (pinfunction "VSS_6") (pintype "bidirectional"))
    )
    (net (code "42") (name "/VBAT_IN") (class "Default")
      (node (ref "D8") (pin "A") (pinfunction "A_A") (pintype "passive"))
      (node (ref "Q3") (pin "3") (pinfunction "D_3") (pintype "passive"))
      (node (ref "R40") (pin "1") (pinfunction "1_1") (pintype "passive"))
      (node (ref "SW2") (pin "2") (pinfunction "D_2") (pintype "bidirectional"))
    )
    (net (code "43") (name "/VBUS") (class "Default")
      (node (ref "C23") (pin "1") (pinfunction "1_1") (pintype "passive"))
      (node (ref "D2") (pin "A") (pinfunction "A_A") (pintype "passive"))
      (node (ref "D9") (pin "COM") (pinfunction "+_COM") (pintype "bidirectional"))
      (node (ref "J1") (pin "VBUS") (pinfunction "VBUS_VBUS") (pintype "power_in"))
      (node (ref "POWER") (pin "+") (pinfunction "1_+") (pintype "bidirectional"))
      (node (ref "Q3") (pin "1") (pinfunction "G_1") (pintype "passive"))
      (node (ref "R13") (pin "2") (pinfunction "2_2") (pintype "passive"))
      (node (ref "R16") (pin "1") (pinfunction "1_1") (pintype "passive"))
      (node (ref "U6") (pin "4") (pinfunction "VIN_4") (pintype "bidirectional"))
      (node (ref "U6") (pin "8") (pinfunction "CE_8") (pintype "bidirectional"))
    )
    (net (code "44") (name "/VDDCORE") (class "Default")
      (node (ref "C7") (pin "1") (pinfunction "1_1") (pintype "passive"))
      (node (ref "IC2") (pin "43") (pinfunction "VDDCORE1_43") (pintype "input"))
    )
    (net (code "45") (name "/VIN") (class "Default")
      (node (ref "C10") (pin "2") (pinfunction "2_2") (pintype "passive"))
      (node (ref "C18") (pin "2") (pinfunction "2_2") (pintype "passive"))
      (node (ref "D3") (pin "C") (pinfunction "C_C") (pintype "passive"))
      (node (ref "D4") (pin "A") (pinfunction "A_A") (pintype "passive"))
      (node (ref "D8") (pin "C") (pinfunction "C_C") (pintype "passive"))
      (node (ref "Q3") (pin "2") (pinfunction "S_2") (pintype "passive"))
      (node (ref "Q9") (pin "3") (pinfunction "D_3") (pintype "passive"))
      (node (ref "R33") (pin "2") (pinfunction "2_2") (pintype "passive"))
      (node (ref "U5") (pin "5") (pinfunction "EN_5") (pintype "bidirectional"))
      (node (ref "U5") (pin "8") (pinfunction "IN_8") (pintype "input"))
    )
    (net (code "46") (name "/VIO") (class "Default")
      (node (ref "R14") (pin "2") (pinfunction "2_2") (pintype "passive"))
      (node (ref "U2") (pin "43") (pinfunction "VIO_43") (pintype "bidirectional"))
    )
    (net (code "47") (name "A4") (class "Default")
      (node (ref "IC2") (pin "10") (pinfunction "PA5/EIC/AIN5/SCOM0PAD1/TC0_10") (pintype "bidirectional"))
      (node (ref "J9") (pin "1") (pinfunction "1_1") (pintype "bidirectional"))
    )
    (net (code "48") (name "A5") (class "Default")
      (node (ref "IC2") (pin "47") (pinfunction "PB2/EIC/AIN10/SCOM5PAD0_47") (pintype "bidirectional"))
      (node (ref "J9") (pin "2") (pinfunction "2_2") (pintype "bidirectional"))
    )
    (net (code "49") (name "GND") (class "Default")
      (node (ref "C1") (pin "2") (pinfunction "2_2") (pintype "passive"))
      (node (ref "C10") (pin "1") (pinfunction "1_1") (pintype "passive"))
      (node (ref "C11") (pin "1") (pinfunction "1_1") (pintype "passive"))
      (node (ref "C12") (pin "1") (pinfunction "1_1") (pintype "passive"))
      (node (ref "C13") (pin "1") (pinfunction "1_1") (pintype "passive"))
      (node (ref "C14") (pin "1") (pinfunction "1_1") (pintype "passive"))
      (node (ref "C15") (pin "2") (pinfunction "2_2") (pintype "passive"))
      (node (ref "C16") (pin "1") (pinfunction "1_1") (pintype "passive"))
      (node (ref "C17") (pin "C") (pinfunction "-_C") (pintype "passive"))
      (node (ref "C18") (pin "1") (pinfunction "1_1") (pintype "passive"))
      (node (ref "C19") (pin "2") (pinfunction "2_2") (pintype "passive"))
      (node (ref "C2") (pin "2") (pinfunction "2_2") (pintype "passive"))
      (node (ref "C20") (pin "1") (pinfunction "1_1") (pintype "passive"))
      (node (ref "C21") (pin "1") (pinfunction "1_1") (pintype "passive"))
      (node (ref "C22") (pin "2") (pinfunction "2_2") (pintype "passive"))
      (node (ref "C23") (pin "2") (pinfunction "2_2") (pintype "passive"))
      (node (ref "C24") (pin "1") (pinfunction "1_1") (pintype "passive"))
      (node (ref "C26") (pin "1") (pinfunction "1_1") (pintype "passive"))
      (node (ref "C27") (pin "1") (pinfunction "1_1") (pintype "passive"))
      (node (ref "C28") (pin "1") (pinfunction "1_1") (pintype "passive"))
      (node (ref "C29") (pin "1") (pinfunction "1_1") (pintype "passive"))
      (node (ref "C3") (pin "1") (pinfunction "1_1") (pintype "passive"))
      (node (ref "C30") (pin "1") (pinfunction "1_1") (pintype "passive"))
      (node (ref "C31") (pin "1") (pinfunction "1_1") (pintype "passive"))
      (node (ref "C32") (pin "2") (pinfunction "2_2") (pintype "passive"))
      (node (ref "C33") (pin "C") (pinfunction "-_C") (pintype "passive"))
      (node (ref "C34") (pin "2") (pinfunction "2_2") (pintype "passive"))
      (node (ref "C35") (pin "2") (pinfunction "2_2") (pintype "passive"))
      (node (ref "C36") (pin "C") (pinfunction "-_C") (pintype "passive"))
      (node (ref "C4") (pin "2") (pinfunction "2_2") (pintype "passive"))
      (node (ref "C47") (pin "2") (pinfunction "2_2") (pintype "passive"))
      (node (ref "C48") (pin "2") (pinfunction "2_2") (pintype "passive"))
      (node (ref "C49") (pin "2") (pinfunction "2_2") (pintype "passive"))
      (node (ref "C5") (pin "2") (pinfunction "2_2") (pintype "passive"))
      (node (ref "C50") (pin "2") (pinfunction "2_2") (pintype "passive"))
      (node (ref "C51") (pin "2") (pinfunction "2_2") (pintype "passive"))
      (node (ref "C6") (pin "2") (pinfunction "2_2") (pintype "passive"))
      (node (ref "C7") (pin "2") (pinfunction "2_2") (pintype "passive"))
      (node (ref "C8") (pin "2") (pinfunction "2_2") (pintype "passive"))
      (node (ref "C9") (pin "2") (pinfunction "2_2") (pintype "passive"))
      (node (ref "CN2") (pin "3") (pinfunction "3_3") (pintype "passive"))
      (node (ref "CN2") (pin "5") (pinfunction "5_5") (pintype "passive"))
      (node (ref "CN2") (pin "9") (pinfunction "9_9") (pintype "passive"))
      (node (ref "D1") (pin "2") (pinfunction "A_2") (pintype "passive"))
      (node (ref "D5") (pin "2") (pinfunction "A_2") (pintype "passive"))
      (node (ref "DHT11") (pin "1") (pinfunction "P$1_1") (pintype "bidirectional"))
      (node (ref "GND") (pin "T") (pinfunction "T_T") (pintype "bidirectional"))
      (node (ref "GPS") (pin "GND1") (pinfunction "GND1_GND1") (pintype "bidirectional"))
      (node (ref "GPS") (pin "GND2") (pinfunction "GND2_GND2") (pintype "bidirectional"))
      (node (ref "GPS") (pin "GND3") (pinfunction "GND3_GND3") (pintype "bidirectional"))
      (node (ref "GSM") (pin "GND1") (pinfunction "GND1_GND1") (pintype "bidirectional"))
      (node (ref "GSM") (pin "GND2") (pinfunction "GND2_GND2") (pintype "bidirectional"))
      (node (ref "GSM") (pin "GND3") (pinfunction "GND3_GND3") (pintype "bidirectional"))
      (node (ref "IC2") (pin "18") (pinfunction "GND1_18") (pintype "power_in"))
      (node (ref "IC2") (pin "35") (pinfunction "GND2_35") (pintype "power_in"))
      (node (ref "IC2") (pin "42") (pinfunction "GND3_42") (pintype "power_in"))
      (node (ref "IC2") (pin "5") (pinfunction "GNDANA_5") (pintype "power_in"))
      (node (ref "J1") (pin "GND") (pinfunction "GND_GND") (pintype "power_in"))
      (node (ref "J1") (pin "P1") (pinfunction "SHIELD_P1") (pintype "bidirectional"))
      (node (ref "J1") (pin "P2") (pinfunction "SHIELD_P2") (pintype "bidirectional"))
      (node (ref "J1") (pin "P3") (pinfunction "SHIELD_P3") (pintype "bidirectional"))
      (node (ref "J2") (pin "1") (pinfunction "1_1") (pintype "bidirectional"))
      (node (ref "J3") (pin "2") (pinfunction "2_2") (pintype "bidirectional"))
      (node (ref "J3") (pin "4") (pinfunction "4_4") (pintype "bidirectional"))
      (node (ref "J7") (pin "3") (pinfunction "P$3_3") (pintype "bidirectional"))
      (node (ref "J8") (pin "4") (pinfunction "4_4") (pintype "bidirectional"))
      (node (ref "J8") (pin "SS1") (pinfunction "SS1_SS1") (pintype "bidirectional"))
      (node (ref "J8") (pin "SS2") (pinfunction "SS2_SS2") (pintype "bidirectional"))
      (node (ref "J9") (pin "4") (pinfunction "4_4") (pintype "bidirectional"))
      (node (ref "J9") (pin "SS1") (pinfunction "SS1_SS1") (pintype "bidirectional"))
      (node (ref "J9") (pin "SS2") (pinfunction "SS2_SS2") (pintype "bidirectional"))
      (node (ref "NET") (pin "-") (pinfunction "-_-") (pintype "passive"))
      (node (ref "POWER") (pin "-") (pinfunction "2_-") (pintype "bidirectional"))
      (node (ref "POWER") (pin "3") (pinfunction "3_3") (pintype "bidirectional"))
      (node (ref "POWER") (pin "4") (pinfunction "4_4") (pintype "bidirectional"))
      (node (ref "Q1") (pin "2") (pinfunction "E_2") (pintype "passive"))
      (node (ref "Q10") (pin "2") (pinfunction "E_2") (pintype "passive"))
      (node (ref "Q2") (pin "2") (pinfunction "S_2") (pintype "passive"))
      (node (ref "Q5") (pin "2") (pinfunction "S_2") (pintype "passive"))
      (node (ref "Q7") (pin "2") (pinfunction "S_2") (pintype "passive"))
      (node (ref "R15") (pin "1") (pinfunction "1_1") (pintype "passive"))
      (node (ref "R16") (pin "2") (pinfunction "2_2") (pintype "passive"))
      (node (ref "R18") (pin "1") (pinfunction "1_1") (pintype "passive"))
      (node (ref "R19") (pin "1") (pinfunction "1_1") (pintype "passive"))
      (node (ref "R22") (pin "1") (pinfunction "1_1") (pintype "passive"))
      (node (ref "R28") (pin "1") (pinfunction "1_1") (pintype "passive"))
      (node (ref "R29") (pin "1") (pinfunction "1_1") (pintype "passive"))
      (node (ref "R35") (pin "2") (pinfunction "2_2") (pintype "passive"))
      (node (ref "R37") (pin "1") (pinfunction "1_1") (pintype "passive"))
      (node (ref "R39") (pin "1") (pinfunction "1_1") (pintype "passive"))
      (node (ref "R44") (pin "1") (pinfunction "1_1") (pintype "passive"))
      (node (ref "R47") (pin "1") (pinfunction "1_1") (pintype "passive"))
      (node (ref "R50") (pin "2") (pinfunction "2_2") (pintype "passive"))
      (node (ref "R51") (pin "2") (pinfunction "2_2") (pintype "passive"))
      (node (ref "R55") (pin "1") (pinfunction "1_1") (pintype "passive"))
      (node (ref "RST") (pin "2") (pinfunction "2_2") (pintype "passive"))
      (node (ref "S9") (pin "1") (pinfunction "1_1") (pintype "bidirectional"))
      (node (ref "S9") (pin "2") (pinfunction "2_2") (pintype "bidirectional"))
      (node (ref "SD") (pin "6") (pinfunction "VSS_6") (pintype "bidirectional"))
      (node (ref "SD") (pin "G1") (pinfunction "G1_G1") (pintype "bidirectional"))
      (node (ref "SD") (pin "G2") (pinfunction "G2_G2") (pintype "bidirectional"))
      (node (ref "SD") (pin "G3") (pinfunction "G3_G3") (pintype "bidirectional"))
      (node (ref "SD") (pin "G4") (pinfunction "G4_G4") (pintype "bidirectional"))
      (node (ref "SIM1") (pin "5") (pinfunction "GND_5") (pintype "bidirectional"))
      (node (ref "STA") (pin "-") (pinfunction "-_-") (pintype "passive"))
      (node (ref "SW2") (pin "4") (pinfunction "GND_4") (pintype "bidirectional"))
      (node (ref "SW2") (pin "5") (pinfunction "GND_5") (pintype "bidirectional"))
      (node (ref "U1") (pin "1") (pinfunction "GND_1") (pintype "power_in"))
      (node (ref "U1") (pin "7") (pinfunction "GND_7") (pintype "power_in"))
      (node (ref "U2") (pin "10") (pinfunction "GND_10") (pintype "bidirectional"))
      (node (ref "U2") (pin "27") (pinfunction "GND_27") (pintype "bidirectional"))
      (node (ref "U2") (pin "29") (pinfunction "GND_29") (pintype "bidirectional"))
      (node (ref "U2") (pin "44") (pinfunction "GND_44") (pintype "bidirectional"))
      (node (ref "U2") (pin "46") (pinfunction "GND_46") (pintype "bidirectional"))
      (node (ref "U2") (pin "55") (pinfunction "GND_55") (pintype "bidirectional"))
      (node (ref "U2") (pin "56") (pinfunction "GND_56") (pintype "bidirectional"))
      (node (ref "U3") (pin "1") (pinfunction "ADR_1") (pintype "bidirectional"))
      (node (ref "U3") (pin "5") (pinfunction "GND_5") (pintype "bidirectional"))
      (node (ref "U4") (pin "2") (pinfunction "GND_2") (pintype "bidirectional"))
      (node (ref "U5") (pin "4") (pinfunction "GND_4") (pintype "input"))
      (node (ref "U5") (pin "EP") (pinfunction "GND_EP") (pintype "input"))
      (node (ref "U6") (pin "1") (pinfunction "TEMP_1") (pintype "bidirectional"))
      (node (ref "U6") (pin "3") (pinfunction "GND_3") (pintype "bidirectional"))
      (node (ref "U6") (pin "9") (pinfunction "GND_9") (pintype "bidirectional"))
      (node (ref "U7") (pin "2") (pinfunction "S1_2") (pintype "bidirectional"))
      (node (ref "WIND") (pin "2") (pinfunction "P$2_2") (pintype "bidirectional"))
    )
    (net (code "50") (name "Net-(BUZZER-P$4)") (class "Default")
      (node (ref "BUZZER") (pin "4") (pinfunction "P$4_4") (pintype "bidirectional"))
      (node (ref "Q1") (pin "3") (pinfunction "C_3") (pintype "passive"))
    )
    (net (code "51") (name "Net-(C13-Pad2)") (class "Default")
      (node (ref "C13") (pin "2") (pinfunction "2_2") (pintype "passive"))
      (node (ref "GSM") (pin "D") (pinfunction "D_D") (pintype "bidirectional"))
      (node (ref "R7") (pin "2") (pinfunction "2_2") (pintype "passive"))
    )
    (net (code "52") (name "Net-(C33-+)") (class "Default")
      (node (ref "C32") (pin "1") (pinfunction "1_1") (pintype "passive"))
      (node (ref "C33") (pin "A") (pinfunction "+_A") (pintype "passive"))
      (node (ref "C34") (pin "1") (pinfunction "1_1") (pintype "passive"))
      (node (ref "C35") (pin "1") (pinfunction "1_1") (pintype "passive"))
      (node (ref "C36") (pin "A") (pinfunction "+_A") (pintype "passive"))
      (node (ref "J3") (pin "1") (pinfunction "1_1") (pintype "bidirectional"))
      (node (ref "R52") (pin "2") (pinfunction "2_2") (pintype "passive"))
    )
    (net (code "53") (name "Net-(D2-PadC)") (class "Default")
      (node (ref "D2") (pin "C") (pinfunction "C_C") (pintype "passive"))
      (node (ref "D3") (pin "A") (pinfunction "A_A") (pintype "passive"))
    )
    (net (code "54") (name "Net-(D9-G)") (class "Default")
      (node (ref "D9") (pin "1") (pinfunction "G_1") (pintype "bidirectional"))
      (node (ref "R32") (pin "2") (pinfunction "2_2") (pintype "passive"))
    )
    (net (code "55") (name "Net-(D9-R)") (class "Default")
      (node (ref "D9") (pin "2") (pinfunction "R_2") (pintype "bidirectional"))
      (node (ref "R31") (pin "2") (pinfunction "2_2") (pintype "passive"))
    )
    (net (code "56") (name "Net-(J3-Pad5)") (class "Default")
      (node (ref "J3") (pin "5") (pinfunction "5_5") (pintype "bidirectional"))
      (node (ref "R54") (pin "1") (pinfunction "1_1") (pintype "passive"))
    )
    (net (code "57") (name "Net-(L2-2)") (class "Default")
      (node (ref "D7") (pin "A") (pinfunction "A_A") (pintype "passive"))
      (node (ref "L2") (pin "P$2") (pinfunction "2_P$2") (pintype "passive"))
      (node (ref "U4") (pin "1") (pinfunction "SW_1") (pintype "bidirectional"))
    )
    (net (code "58") (name "Net-(LED1-Pad+)") (class "Default")
      (node (ref "LED1") (pin "+") (pinfunction "+_+") (pintype "passive"))
      (node (ref "R27") (pin "1") (pinfunction "1_1") (pintype "passive"))
    )
    (net (code "59") (name "Net-(NET-Pad+)") (class "Default")
      (node (ref "NET") (pin "+") (pinfunction "+_+") (pintype "passive"))
      (node (ref "R5") (pin "2") (pinfunction "2_2") (pintype "passive"))
    )
    (net (code "60") (name "Net-(Q1-B)") (class "Default")
      (node (ref "Q1") (pin "1") (pinfunction "B_1") (pintype "passive"))
      (node (ref "R25") (pin "2") (pinfunction "2_2") (pintype "passive"))
    )
    (net (code "61") (name "Net-(Q2-D)") (class "Default")
      (node (ref "Q2") (pin "3") (pinfunction "D_3") (pintype "passive"))
      (node (ref "U2") (pin "18") (pinfunction "RESET_18") (pintype "bidirectional"))
    )
    (net (code "62") (name "Net-(Q2-G)") (class "Default")
      (node (ref "Q2") (pin "1") (pinfunction "G_1") (pintype "passive"))
      (node (ref "R18") (pin "2") (pinfunction "2_2") (pintype "passive"))
      (node (ref "R21") (pin "1") (pinfunction "1_1") (pintype "passive"))
    )
    (net (code "63") (name "Net-(Q4-G)") (class "Default")
      (node (ref "C38") (pin "1") (pinfunction "1_1") (pintype "passive"))
      (node (ref "Q4") (pin "1") (pinfunction "G_1") (pintype "passive"))
      (node (ref "R10") (pin "2") (pinfunction "2_2") (pintype "passive"))
    )
    (net (code "64") (name "Net-(Q4-S)") (class "Default")
      (node (ref "C38") (pin "2") (pinfunction "2_2") (pintype "passive"))
      (node (ref "D4") (pin "C") (pinfunction "C_C") (pintype "passive"))
      (node (ref "Q4") (pin "2") (pinfunction "S_2") (pintype "passive"))
      (node (ref "Q9") (pin "2") (pinfunction "S_2") (pintype "passive"))
      (node (ref "R20") (pin "2") (pinfunction "2_2") (pintype "passive"))
      (node (ref "R33") (pin "1") (pinfunction "1_1") (pintype "passive"))
      (node (ref "R34") (pin "2") (pinfunction "2_2") (pintype "passive"))
    )
    (net (code "65") (name "Net-(Q5-D)") (class "Default")
      (node (ref "Q5") (pin "3") (pinfunction "D_3") (pintype "passive"))
      (node (ref "Q9") (pin "1") (pinfunction "G_1") (pintype "passive"))
      (node (ref "R10") (pin "1") (pinfunction "1_1") (pintype "passive"))
      (node (ref "R20") (pin "1") (pinfunction "1_1") (pintype "passive"))
    )
    (net (code "66") (name "Net-(Q5-G)") (class "Default")
      (node (ref "Q5") (pin "1") (pinfunction "G_1") (pintype "passive"))
      (node (ref "R19") (pin "2") (pinfunction "2_2") (pintype "passive"))
      (node (ref "R26") (pin "1") (pinfunction "1_1") (pintype "passive"))
    )
    (net (code "67") (name "Net-(Q6-G)") (class "Default")
      (node (ref "C37") (pin "1") (pinfunction "1_1") (pintype "passive"))
      (node (ref "Q6") (pin "1") (pinfunction "G_1") (pintype "passive"))
      (node (ref "R12") (pin "2") (pinfunction "2_2") (pintype "passive"))
    )
    (net (code "68") (name "Net-(Q6-S)") (class "Default")
      (node (ref "C37") (pin "2") (pinfunction "2_2") (pintype "passive"))
      (node (ref "D6") (pin "C") (pinfunction "C_C") (pintype "passive"))
      (node (ref "Q6") (pin "2") (pinfunction "S_2") (pintype "passive"))
      (node (ref "Q8") (pin "2") (pinfunction "S_2") (pintype "passive"))
      (node (ref "R36") (pin "2") (pinfunction "2_2") (pintype "passive"))
      (node (ref "R42") (pin "2") (pinfunction "2_2") (pintype "passive"))
      (node (ref "R45") (pin "1") (pinfunction "1_1") (pintype "passive"))
    )
    (net (code "69") (name "Net-(Q7-D)") (class "Default")
      (node (ref "Q7") (pin "3") (pinfunction "D_3") (pintype "passive"))
      (node (ref "Q8") (pin "1") (pinfunction "G_1") (pintype "passive"))
      (node (ref "R12") (pin "1") (pinfunction "1_1") (pintype "passive"))
      (node (ref "R36") (pin "1") (pinfunction "1_1") (pintype "passive"))
    )
    (net (code "70") (name "Net-(Q7-G)") (class "Default")
      (node (ref "Q7") (pin "1") (pinfunction "G_1") (pintype "passive"))
      (node (ref "R37") (pin "2") (pinfunction "2_2") (pintype "passive"))
      (node (ref "R41") (pin "1") (pinfunction "1_1") (pintype "passive"))
    )
    (net (code "71") (name "Net-(Q10-B)") (class "Default")
      (node (ref "Q10") (pin "1") (pinfunction "B_1") (pintype "passive"))
      (node (ref "R28") (pin "2") (pinfunction "2_2") (pintype "passive"))
      (node (ref "R53") (pin "1") (pinfunction "1_1") (pintype "passive"))
    )
    (net (code "72") (name "Net-(Q10-C)") (class "Default")
      (node (ref "J3") (pin "3") (pinfunction "3_3") (pintype "bidirectional"))
      (node (ref "Q10") (pin "3") (pinfunction "C_3") (pintype "passive"))
    )
    (net (code "73") (name "Net-(R6-Pad2)") (class "Default")
      (node (ref "R6") (pin "2") (pinfunction "2_2") (pintype "passive"))
      (node (ref "STA") (pin "+") (pinfunction "+_+") (pintype "passive"))
    )
    (net (code "74") (name "Net-(U1-SDO)") (class "Default")
      (node (ref "R3") (pin "1") (pinfunction "1_1") (pintype "passive"))
      (node (ref "R47") (pin "2") (pinfunction "2_2") (pintype "passive"))
      (node (ref "U1") (pin "5") (pinfunction "SDO_5") (pintype "bidirectional"))
    )
    (net (code "75") (name "Net-(U2-UART1_RXD)") (class "Default")
      (node (ref "R49") (pin "2") (pinfunction "2_2") (pintype "passive"))
      (node (ref "U2") (pin "53") (pinfunction "UART1_RXD_53") (pintype "bidirectional"))
    )
    (net (code "76") (name "Net-(U2-UART1_TXD)") (class "Default")
      (node (ref "R48") (pin "2") (pinfunction "2_2") (pintype "passive"))
      (node (ref "U2") (pin "54") (pinfunction "UART1_TXD_54") (pintype "bidirectional"))
    )
    (net (code "77") (name "Net-(U4-FB)") (class "Default")
      (node (ref "C52") (pin "2") (pinfunction "2_2") (pintype "passive"))
      (node (ref "R46") (pin "2") (pinfunction "2_2") (pintype "passive"))
      (node (ref "R50") (pin "1") (pinfunction "1_1") (pintype "passive"))
      (node (ref "U4") (pin "3") (pinfunction "FB_3") (pintype "bidirectional"))
    )
    (net (code "78") (name "Net-(U4-NC)") (class "Default")
      (node (ref "R51") (pin "1") (pinfunction "1_1") (pintype "passive"))
      (node (ref "U4") (pin "6") (pinfunction "NC_6") (pintype "bidirectional"))
    )
    (net (code "79") (name "Net-(U6-CHRG)") (class "Default")
      (node (ref "R31") (pin "1") (pinfunction "1_1") (pintype "passive"))
      (node (ref "U6") (pin "7") (pinfunction "CHRG_7") (pintype "bidirectional"))
    )
    (net (code "80") (name "Net-(U6-DONE)") (class "Default")
      (node (ref "R32") (pin "1") (pinfunction "1_1") (pintype "passive"))
      (node (ref "U6") (pin "6") (pinfunction "DONE_6") (pintype "bidirectional"))
    )
    (net (code "81") (name "Net-(U6-ISET)") (class "Default")
      (node (ref "R29") (pin "2") (pinfunction "2_2") (pintype "passive"))
      (node (ref "U6") (pin "2") (pinfunction "ISET_2") (pintype "bidirectional"))
    )
    (net (code "82") (name "Net-(U7-V)") (class "Default")
      (node (ref "R22") (pin "2") (pinfunction "2_2") (pintype "passive"))
      (node (ref "U7") (pin "1") (pinfunction "V_1") (pintype "bidirectional"))
    )
    (net (code "83") (name "Net-(U7-VDD)") (class "Default")
      (node (ref "C25") (pin "2") (pinfunction "2_2") (pintype "passive"))
      (node (ref "R24") (pin "2") (pinfunction "2_2") (pintype "passive"))
      (node (ref "U7") (pin "5") (pinfunction "VDD_5") (pintype "bidirectional"))
    )
    (net (code "84") (name "Net-(WIND-P$3)") (class "Default")
      (node (ref "R17") (pin "1") (pinfunction "1_1") (pintype "passive"))
      (node (ref "R38") (pin "1") (pinfunction "1_1") (pintype "passive"))
      (node (ref "WIND") (pin "3") (pinfunction "P$3_3") (pintype "bidirectional"))
    )
    (net (code "85") (name "RESET") (class "Default")
      (node (ref "C20") (pin "2") (pinfunction "2_2") (pintype "passive"))
      (node (ref "CN2") (pin "10") (pinfunction "10_10") (pintype "passive"))
      (node (ref "IC2") (pin "40") (pinfunction "RESETN_40") (pintype "bidirectional"))
      (node (ref "R8") (pin "1") (pinfunction "1_1") (pintype "passive"))
      (node (ref "RST") (pin "1") (pinfunction "1_1") (pintype "passive"))
    )
    (net (code "86") (name "SCL") (class "Default")
      (node (ref "IC2") (pin "32") (pinfunction "PA23/I2C/EIC/SCOM5PAD1+/TC4_32") (pintype "bidirectional"))
      (node (ref "J2") (pin "3") (pinfunction "3_3") (pintype "bidirectional"))
      (node (ref "J8") (pin "1") (pinfunction "1_1") (pintype "bidirectional"))
      (node (ref "R4") (pin "1") (pinfunction "1_1") (pintype "passive"))
      (node (ref "R9") (pin "1") (pinfunction "1_1") (pintype "passive"))
      (node (ref "U1") (pin "4") (pinfunction "SCK_4") (pintype "bidirectional"))
      (node (ref "U3") (pin "3") (pinfunction "SCL_3") (pintype "bidirectional"))
    )
    (net (code "87") (name "SDA") (class "Default")
      (node (ref "IC2") (pin "31") (pinfunction "PA22/I2C/EIC/SCOM5PAD0+/TC4_31") (pintype "bidirectional"))
      (node (ref "J2") (pin "4") (pinfunction "4_4") (pintype "bidirectional"))
      (node (ref "J8") (pin "2") (pinfunction "2_2") (pintype "bidirectional"))
      (node (ref "R1") (pin "1") (pinfunction "1_1") (pintype "passive"))
      (node (ref "R11") (pin "1") (pinfunction "1_1") (pintype "passive"))
      (node (ref "U1") (pin "3") (pinfunction "SDI_3") (pintype "bidirectional"))
      (node (ref "U3") (pin "2") (pinfunction "SDA_2") (pintype "bidirectional"))
    )
    (net (code "88") (name "VBAT+") (class "Default")
      (node (ref "BAT") (pin "1") (pinfunction "1_1") (pintype "bidirectional"))
      (node (ref "C22") (pin "1") (pinfunction "1_1") (pintype "passive"))
      (node (ref "R24") (pin "1") (pinfunction "1_1") (pintype "passive"))
      (node (ref "R40") (pin "2") (pinfunction "2_2") (pintype "passive"))
      (node (ref "SW2") (pin "1") (pinfunction "D_1") (pintype "bidirectional"))
      (node (ref "U6") (pin "5") (pinfunction "BAT_5") (pintype "bidirectional"))
    )
    (net (code "89") (name "VCC") (class "Default")
      (node (ref "C1") (pin "1") (pinfunction "1_1") (pintype "passive"))
      (node (ref "C2") (pin "1") (pinfunction "1_1") (pintype "passive"))
      (node (ref "C21") (pin "2") (pinfunction "2_2") (pintype "passive"))
      (node (ref "C24") (pin "2") (pinfunction "2_2") (pintype "passive"))
      (node (ref "C28") (pin "2") (pinfunction "2_2") (pintype "passive"))
      (node (ref "C29") (pin "2") (pinfunction "2_2") (pintype "passive"))
      (node (ref "C30") (pin "2") (pinfunction "2_2") (pintype "passive"))
      (node (ref "C31") (pin "2") (pinfunction "2_2") (pintype "passive"))
      (node (ref "D1") (pin "4") (pinfunction "C3_4") (pintype "passive"))
      (node (ref "DHT11") (pin "4") (pinfunction "P$4_4") (pintype "bidirectional"))
      (node (ref "J2") (pin "2") (pinfunction "2_2") (pintype "bidirectional"))
      (node (ref "J8") (pin "3") (pinfunction "3_3") (pintype "bidirectional"))
      (node (ref "J9") (pin "3") (pinfunction "3_3") (pintype "bidirectional"))
      (node (ref "Q6") (pin "3") (pinfunction "D_3") (pintype "passive"))
      (node (ref "R1") (pin "2") (pinfunction "2_2") (pintype "passive"))
      (node (ref "R3") (pin "2") (pinfunction "2_2") (pintype "passive"))
      (node (ref "R30") (pin "2") (pinfunction "2_2") (pintype "passive"))
      (node (ref "R4") (pin "2") (pinfunction "2_2") (pintype "passive"))
      (node (ref "R42") (pin "1") (pinfunction "1_1") (pintype "passive"))
      (node (ref "SD") (pin "4") (pinfunction "VDD_4") (pintype "bidirectional"))
      (node (ref "U1") (pin "2") (pinfunction "CSB_2") (pintype "bidirectional"))
      (node (ref "U1") (pin "6") (pinfunction "VDDIO_6") (pintype "power_in"))
      (node (ref "U1") (pin "8") (pinfunction "VDD_8") (pintype "power_in"))
      (node (ref "U3") (pin "4") (pinfunction "VDD_4") (pintype "bidirectional"))
    )
    (net (code "90") (name "VDD") (class "Default")
      (node (ref "BUZZER") (pin "1") (pinfunction "P$1_1") (pintype "bidirectional"))
      (node (ref "C12") (pin "2") (pinfunction "2_2") (pintype "passive"))
      (node (ref "C16") (pin "2") (pinfunction "2_2") (pintype "passive"))
      (node (ref "C17") (pin "A") (pinfunction "+_A") (pintype "passive"))
      (node (ref "C47") (pin "1") (pinfunction "1_1") (pintype "passive"))
      (node (ref "C48") (pin "1") (pinfunction "1_1") (pintype "passive"))
      (node (ref "L1") (pin "2") (pinfunction "2_2") (pintype "passive"))
      (node (ref "L2") (pin "P$1") (pinfunction "1_P$1") (pintype "passive"))
      (node (ref "Q4") (pin "3") (pinfunction "D_3") (pintype "passive"))
      (node (ref "R34") (pin "1") (pinfunction "1_1") (pintype "passive"))
      (node (ref "R43") (pin "2") (pinfunction "2_2") (pintype "passive"))
      (node (ref "U2") (pin "11") (pinfunction "VBAT_11") (pintype "bidirectional"))
      (node (ref "U2") (pin "12") (pinfunction "VBAT_12") (pintype "bidirectional"))
      (node (ref "U4") (pin "4") (pinfunction "EN_4") (pintype "bidirectional"))
      (node (ref "U4") (pin "5") (pinfunction "VIN_5") (pintype "bidirectional"))
    )
    (net (code "91") (name "unconnected-(BUZZER-P$2-Pad2)") (class "Default")
      (node (ref "BUZZER") (pin "2") (pinfunction "P$2_2") (pintype "bidirectional"))
    )
    (net (code "92") (name "unconnected-(BUZZER-P$3-Pad3)") (class "Default")
      (node (ref "BUZZER") (pin "3") (pinfunction "P$3_3") (pintype "bidirectional"))
    )
    (net (code "93") (name "unconnected-(CN2-Pad6)") (class "Default")
      (node (ref "CN2") (pin "6") (pinfunction "6_6") (pintype "passive"))
    )
    (net (code "94") (name "unconnected-(CN2-Pad7)") (class "Default")
      (node (ref "CN2") (pin "7") (pinfunction "7_7") (pintype "passive"))
    )
    (net (code "95") (name "unconnected-(CN2-Pad8)") (class "Default")
      (node (ref "CN2") (pin "8") (pinfunction "8_8") (pintype "passive"))
    )
    (net (code "96") (name "unconnected-(D5-C5-Pad6)") (class "Default")
      (node (ref "D5") (pin "6") (pinfunction "C5_6") (pintype "passive"))
    )
    (net (code "97") (name "unconnected-(DHT11-P$2-Pad2)") (class "Default")
      (node (ref "DHT11") (pin "2") (pinfunction "P$2_2") (pintype "bidirectional"))
    )
    (net (code "98") (name "unconnected-(IC2-PA13{slash}I2C{slash}EIC{slash}SCOM2PAD1+{slash}TC2-Pad22)") (class "Default")
      (node (ref "IC2") (pin "22") (pinfunction "PA13/I2C/EIC/SCOM2PAD1+/TC2_22") (pintype "bidirectional"))
    )
    (net (code "99") (name "unconnected-(IC2-PA27{slash}EIC-Pad39)") (class "Default")
      (node (ref "IC2") (pin "39") (pinfunction "PA27/EIC_39") (pintype "bidirectional"))
    )
    (net (code "100") (name "unconnected-(IC2-PA28{slash}EIC-Pad41)") (class "Default")
      (node (ref "IC2") (pin "41") (pinfunction "PA28/EIC_41") (pintype "bidirectional"))
    )
    (net (code "101") (name "unconnected-(IC2-PB3{slash}EIC{slash}AIN11{slash}SCOM5PAD1-Pad48)") (class "Default")
      (node (ref "IC2") (pin "48") (pinfunction "PB3/EIC/AIN11/SCOM5PAD1_48") (pintype "bidirectional"))
    )
    (net (code "102") (name "unconnected-(IC2-PB22{slash}EIC{slash}SCOM5PAD2-Pad37)") (class "Default")
      (node (ref "IC2") (pin "37") (pinfunction "PB22/EIC/SCOM5PAD2_37") (pintype "bidirectional"))
    )
    (net (code "103") (name "unconnected-(IC2-PB23{slash}EIC{slash}SCOM5PAD3-Pad38)") (class "Default")
      (node (ref "IC2") (pin "38") (pinfunction "PB23/EIC/SCOM5PAD3_38") (pintype "bidirectional"))
    )
    (net (code "104") (name "unconnected-(J1-PadID)") (class "Default")
      (node (ref "J1") (pin "ID") (pinfunction "ID_ID") (pintype "bidirectional"))
    )
    (net (code "105") (name "unconnected-(SD-CDN-Pad9)") (class "Default")
      (node (ref "SD") (pin "9") (pinfunction "CDN_9") (pintype "bidirectional"))
    )
    (net (code "106") (name "unconnected-(SD-DATA1-Pad8)") (class "Default")
      (node (ref "SD") (pin "8") (pinfunction "DATA1_8") (pintype "bidirectional"))
    )
    (net (code "107") (name "unconnected-(SD-DATA2-Pad1)") (class "Default")
      (node (ref "SD") (pin "1") (pinfunction "DATA2_1") (pintype "bidirectional"))
    )
    (net (code "108") (name "unconnected-(SIM1-VPP-Pad6)") (class "Default")
      (node (ref "SIM1") (pin "6") (pinfunction "VPP_6") (pintype "bidirectional"))
    )
    (net (code "109") (name "unconnected-(SW2-D-Pad3)") (class "Default")
      (node (ref "SW2") (pin "3") (pinfunction "D_3") (pintype "bidirectional"))
    )
    (net (code "110") (name "unconnected-(U2-ADC0-Pad15)") (class "Default")
      (node (ref "U2") (pin "15") (pinfunction "ADC0_15") (pintype "bidirectional"))
    )
    (net (code "111") (name "unconnected-(U2-ADC1-Pad16)") (class "Default")
      (node (ref "U2") (pin "16") (pinfunction "ADC1_16") (pintype "bidirectional"))
    )
    (net (code "112") (name "unconnected-(U2-I2C2_SCL-Pad1)") (class "Default")
      (node (ref "U2") (pin "1") (pinfunction "I2C2_SCL_1") (pintype "bidirectional"))
    )
    (net (code "113") (name "unconnected-(U2-I2C2_SDA-Pad2)") (class "Default")
      (node (ref "U2") (pin "2") (pinfunction "I2C2_SDA_2") (pintype "bidirectional"))
    )
    (net (code "114") (name "unconnected-(U2-IO26-Pad25)") (class "Default")
      (node (ref "U2") (pin "25") (pinfunction "IO26_25") (pintype "bidirectional"))
    )
    (net (code "115") (name "unconnected-(U2-IO29-Pad24)") (class "Default")
      (node (ref "U2") (pin "24") (pinfunction "IO29_24") (pintype "bidirectional"))
    )
    (net (code "116") (name "unconnected-(U2-IO30-Pad31)") (class "Default")
      (node (ref "U2") (pin "31") (pinfunction "IO30_31") (pintype "bidirectional"))
    )
    (net (code "117") (name "unconnected-(U2-LCD_CS-Pad19)") (class "Default")
      (node (ref "U2") (pin "19") (pinfunction "LCD_CS_19") (pintype "bidirectional"))
    )
    (net (code "118") (name "unconnected-(U2-LCD_DIO-Pad21)") (class "Default")
      (node (ref "U2") (pin "21") (pinfunction "LCD_DIO_21") (pintype "bidirectional"))
    )
    (net (code "119") (name "unconnected-(U2-LCD_RST-Pad20)") (class "Default")
      (node (ref "U2") (pin "20") (pinfunction "LCD_RST_20") (pintype "bidirectional"))
    )
    (net (code "120") (name "unconnected-(U2-LCD_SCK-Pad23)") (class "Default")
      (node (ref "U2") (pin "23") (pinfunction "LCD_SCK_23") (pintype "bidirectional"))
    )
    (net (code "121") (name "unconnected-(U2-LCD_SDC-Pad22)") (class "Default")
      (node (ref "U2") (pin "22") (pinfunction "LCD_SDC_22") (pintype "bidirectional"))
    )
    (net (code "122") (name "unconnected-(U2-MIC_N-Pad33)") (class "Default")
      (node (ref "U2") (pin "33") (pinfunction "MIC_N_33") (pintype "bidirectional"))
    )
    (net (code "123") (name "unconnected-(U2-MIC_P-Pad34)") (class "Default")
      (node (ref "U2") (pin "34") (pinfunction "MIC_P_34") (pintype "bidirectional"))
    )
    (net (code "124") (name "unconnected-(U2-SD_CLK-Pad8)") (class "Default")
      (node (ref "U2") (pin "8") (pinfunction "SD_CLK_8") (pintype "bidirectional"))
    )
    (net (code "125") (name "unconnected-(U2-SD_CMD-Pad7)") (class "Default")
      (node (ref "U2") (pin "7") (pinfunction "SD_CMD_7") (pintype "bidirectional"))
    )
    (net (code "126") (name "unconnected-(U2-SD_D0-Pad6)") (class "Default")
      (node (ref "U2") (pin "6") (pinfunction "SD_D0_6") (pintype "bidirectional"))
    )
    (net (code "127") (name "unconnected-(U2-SD_D1-Pad5)") (class "Default")
      (node (ref "U2") (pin "5") (pinfunction "SD_D1_5") (pintype "bidirectional"))
    )
    (net (code "128") (name "unconnected-(U2-SD_D2-Pad4)") (class "Default")
      (node (ref "U2") (pin "4") (pinfunction "SD_D2_4") (pintype "bidirectional"))
    )
    (net (code "129") (name "unconnected-(U2-SD_D3-Pad3)") (class "Default")
      (node (ref "U2") (pin "3") (pinfunction "SD_D3_3") (pintype "bidirectional"))
    )
    (net (code "130") (name "unconnected-(U2-SPK_N-Pad14)") (class "Default")
      (node (ref "U2") (pin "14") (pinfunction "SPK_N_14") (pintype "bidirectional"))
    )
    (net (code "131") (name "unconnected-(U2-SPK_P-Pad13)") (class "Default")
      (node (ref "U2") (pin "13") (pinfunction "SPK_P_13") (pintype "bidirectional"))
    )
    (net (code "132") (name "unconnected-(U2-UART1_CTS-Pad52)") (class "Default")
      (node (ref "U2") (pin "52") (pinfunction "UART1_CTS_52") (pintype "bidirectional"))
    )
    (net (code "133") (name "unconnected-(U2-UART1_RTS-Pad51)") (class "Default")
      (node (ref "U2") (pin "51") (pinfunction "UART1_RTS_51") (pintype "bidirectional"))
    )
    (net (code "134") (name "unconnected-(U2-UART2_CTS-Pad48)") (class "Default")
      (node (ref "U2") (pin "48") (pinfunction "UART2_CTS_48") (pintype "bidirectional"))
    )
    (net (code "135") (name "unconnected-(U2-UART2_RTS-Pad47)") (class "Default")
      (node (ref "U2") (pin "47") (pinfunction "UART2_RTS_47") (pintype "bidirectional"))
    )
    (net (code "136") (name "unconnected-(U2-UART2_RXD-Pad49)") (class "Default")
      (node (ref "U2") (pin "49") (pinfunction "UART2_RXD_49") (pintype "bidirectional"))
    )
    (net (code "137") (name "unconnected-(U2-UART2_TXD-Pad50)") (class "Default")
      (node (ref "U2") (pin "50") (pinfunction "UART2_TXD_50") (pintype "bidirectional"))
    )
    (net (code "138") (name "unconnected-(U2-USB_N-Pad35)") (class "Default")
      (node (ref "U2") (pin "35") (pinfunction "USB_N_35") (pintype "bidirectional"))
    )
    (net (code "139") (name "unconnected-(U2-USB_P-Pad36)") (class "Default")
      (node (ref "U2") (pin "36") (pinfunction "USB_P_36") (pintype "bidirectional"))
    )
    (net (code "140") (name "unconnected-(U2-VUSB-Pad17)") (class "Default")
      (node (ref "U2") (pin "17") (pinfunction "VUSB_17") (pintype "bidirectional"))
    )
    (net (code "141") (name "unconnected-(U3-NC-Pad6)") (class "Default")
      (node (ref "U3") (pin "6") (pinfunction "NC_6") (pintype "bidirectional"))
    )
    (net (code "142") (name "unconnected-(U7-D-Pad4)") (class "Default")
      (node (ref "U7") (pin "4") (pinfunction "D_4") (pintype "bidirectional"))
    )
  )
)
